# ProPrj_AmatronWithOpto_Flex_2026-01-19.net
KiCad netlist of a schematic drawn in EasyEDA Pro
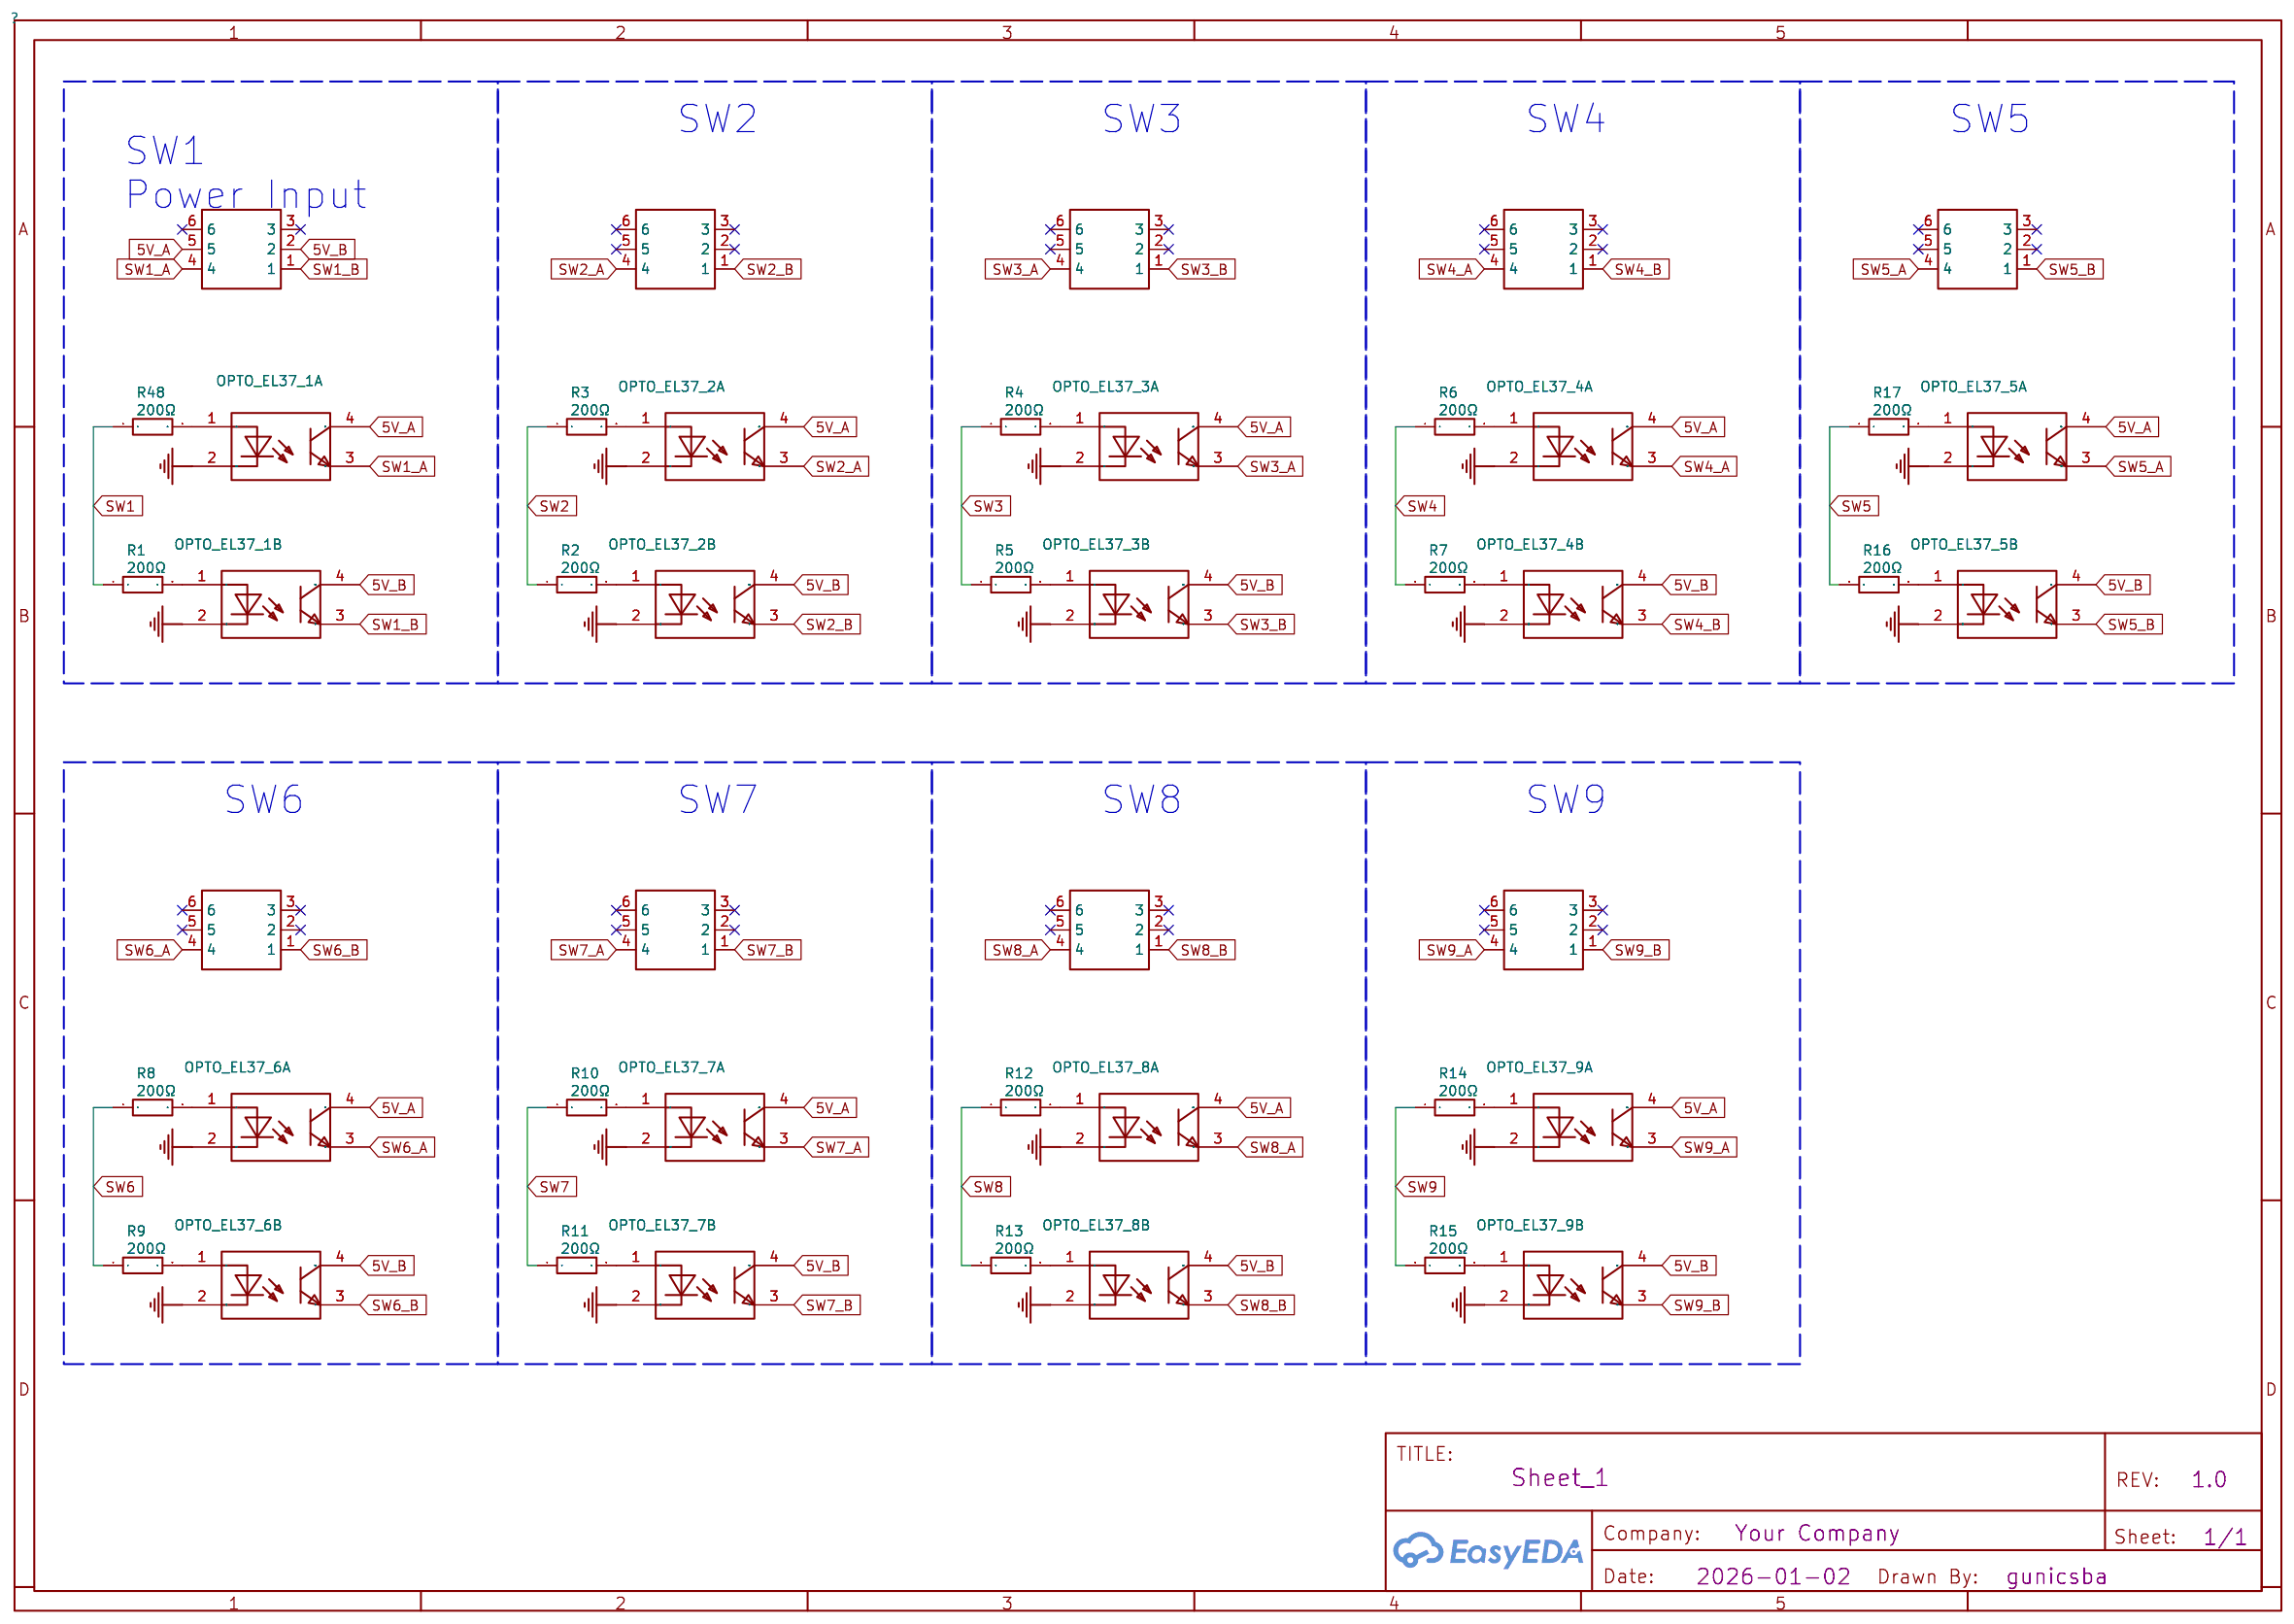
[diagram p0: SWITCH_OPTO]
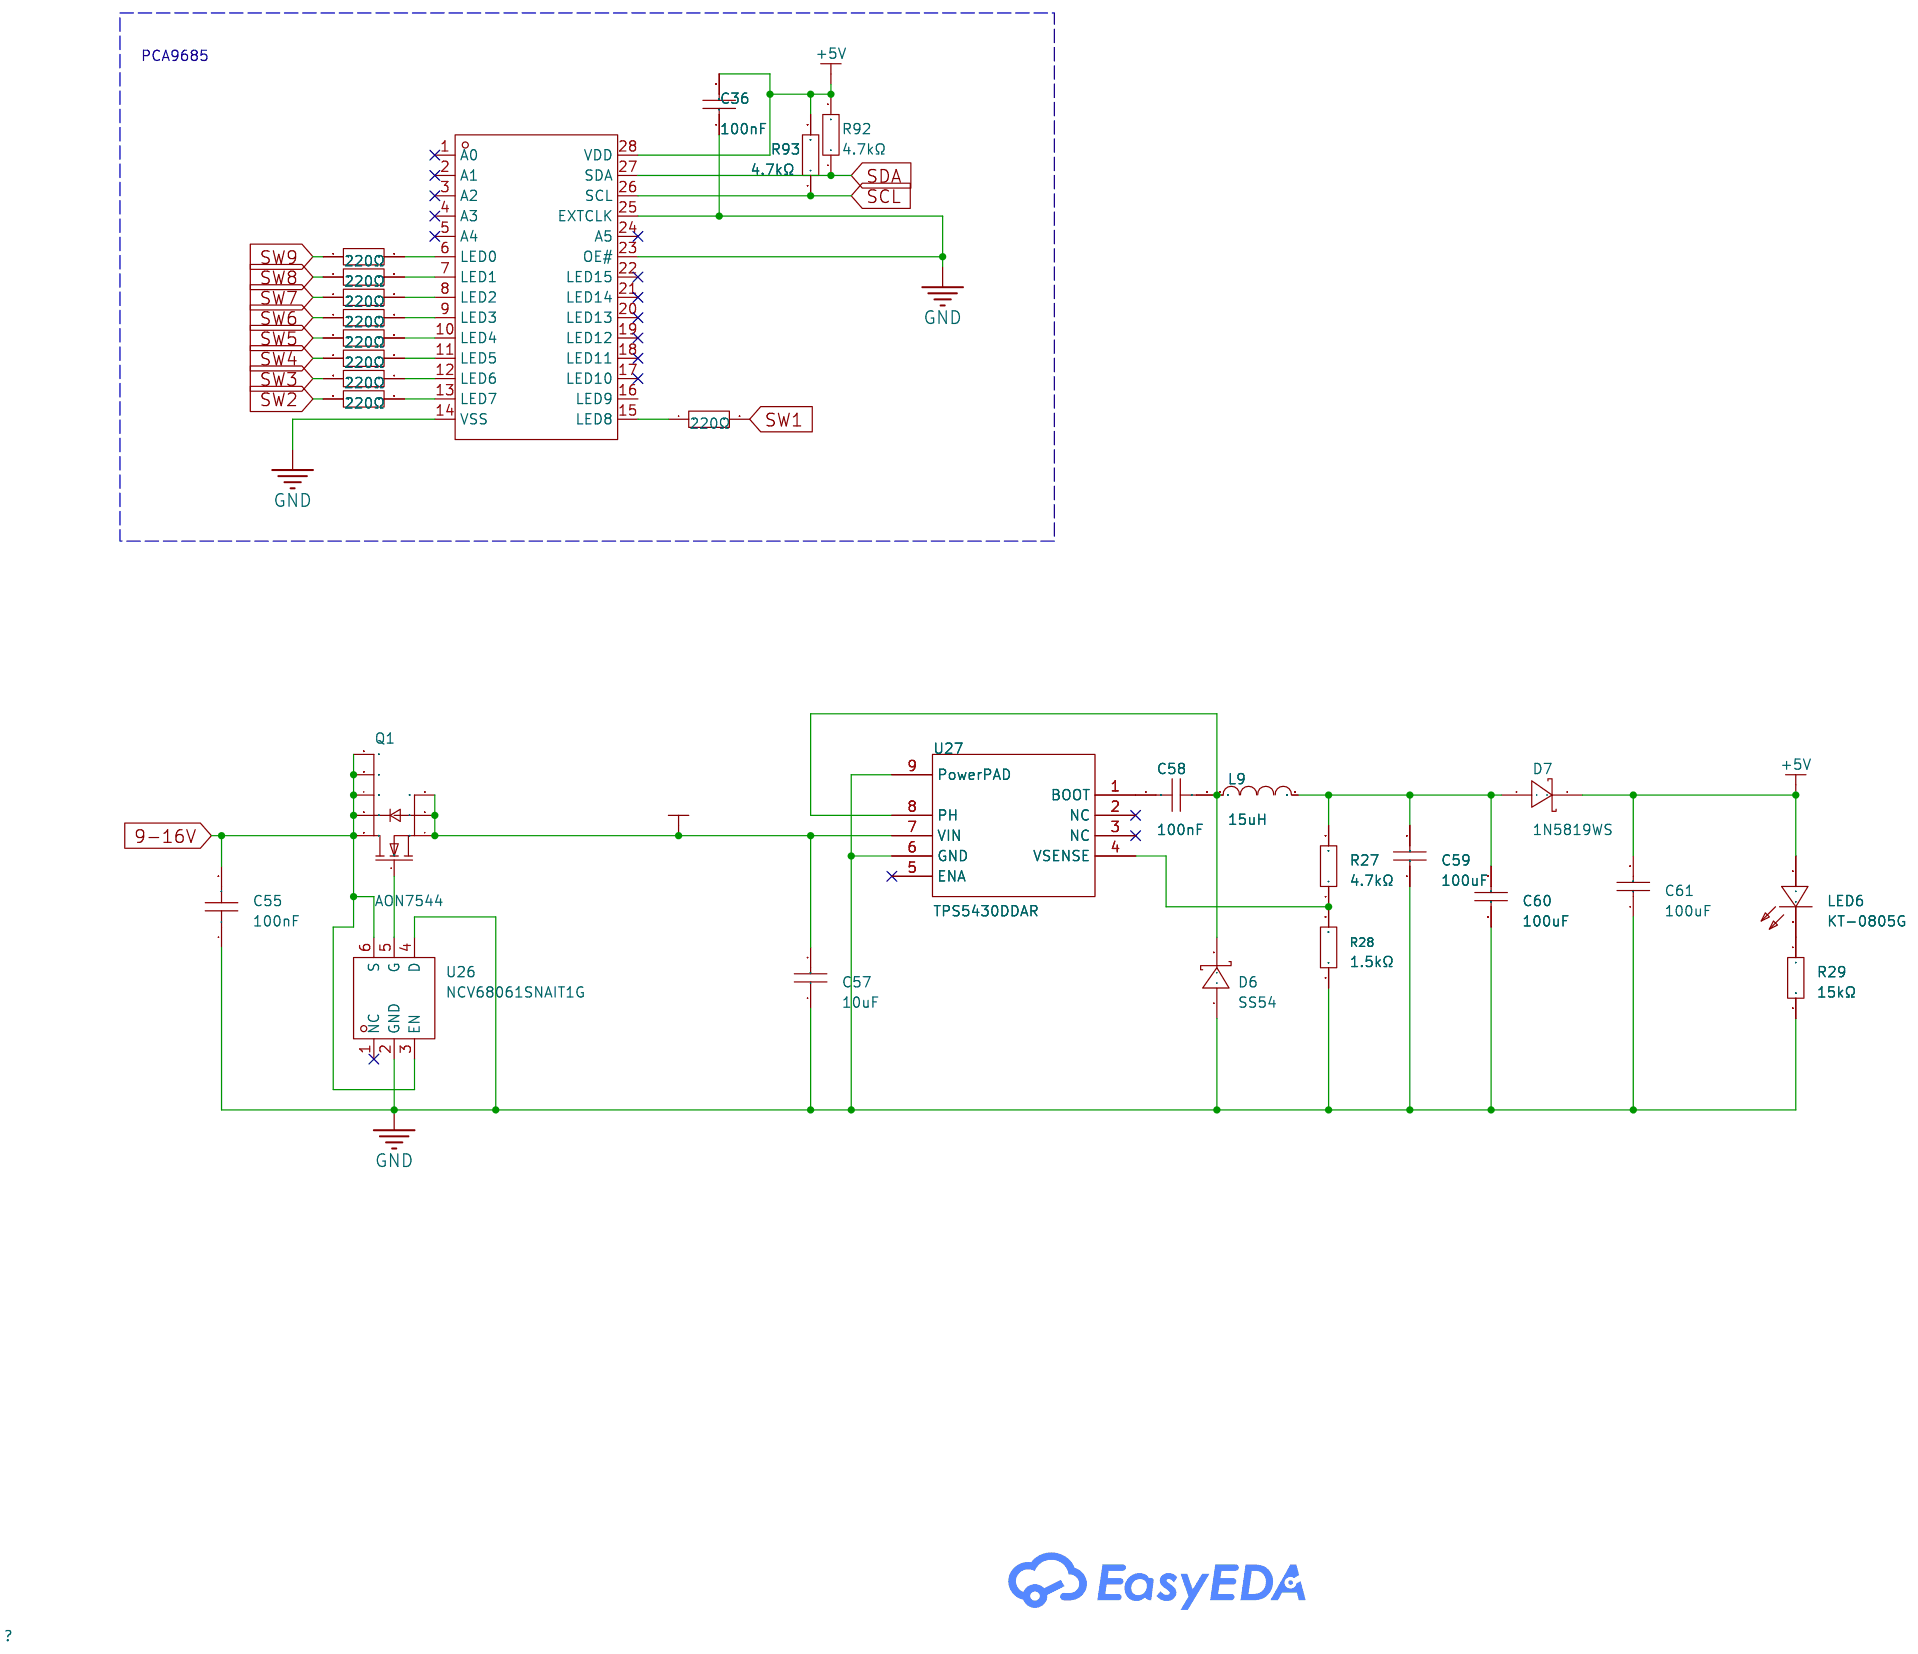
[diagram p1: DRIVER_POWER]

(export (version "E")
  (design (tool "Eeschema 10.0.6"))
  (components
    (comp (ref "OPTO_EL37_1A")
      (value "Speed Pulse")
      (footprint "easyedapro:SOP-4_L4.4-W2.8-P1.27-LS7.0-TL")
      (fields
        (field (name "Manufacturer Part") "EL3H7(B)(TA)-G")
        (field (name "Manufacturer") "EVERLIGHT(亿光)")
      )
      (libsource (lib "easyedapro") (part "Speed Pulse"))
    )
    (comp (ref "OPTO_EL37_1B")
      (value "Speed Pulse")
      (footprint "easyedapro:SOP-4_L4.4-W2.8-P1.27-LS7.0-TL")
      (fields
        (field (name "Manufacturer Part") "EL3H7(B)(TA)-G")
        (field (name "Manufacturer") "EVERLIGHT(亿光)")
      )
      (libsource (lib "easyedapro") (part "Speed Pulse"))
    )
    (comp (ref "OPTO_EL37_2A")
      (value "Speed Pulse")
      (footprint "easyedapro:SOP-4_L4.4-W2.8-P1.27-LS7.0-TL")
      (fields
        (field (name "Manufacturer Part") "EL3H7(B)(TA)-G")
        (field (name "Manufacturer") "EVERLIGHT(亿光)")
      )
      (libsource (lib "easyedapro") (part "Speed Pulse"))
    )
    (comp (ref "OPTO_EL37_2B")
      (value "Speed Pulse")
      (footprint "easyedapro:SOP-4_L4.4-W2.8-P1.27-LS7.0-TL")
      (fields
        (field (name "Manufacturer Part") "EL3H7(B)(TA)-G")
        (field (name "Manufacturer") "EVERLIGHT(亿光)")
      )
      (libsource (lib "easyedapro") (part "Speed Pulse"))
    )
    (comp (ref "OPTO_EL37_3A")
      (value "Speed Pulse")
      (footprint "easyedapro:SOP-4_L4.4-W2.8-P1.27-LS7.0-TL")
      (fields
        (field (name "Manufacturer Part") "EL3H7(B)(TA)-G")
        (field (name "Manufacturer") "EVERLIGHT(亿光)")
      )
      (libsource (lib "easyedapro") (part "Speed Pulse"))
    )
    (comp (ref "OPTO_EL37_3B")
      (value "Speed Pulse")
      (footprint "easyedapro:SOP-4_L4.4-W2.8-P1.27-LS7.0-TL")
      (fields
        (field (name "Manufacturer Part") "EL3H7(B)(TA)-G")
        (field (name "Manufacturer") "EVERLIGHT(亿光)")
      )
      (libsource (lib "easyedapro") (part "Speed Pulse"))
    )
    (comp (ref "OPTO_EL37_4A")
      (value "Speed Pulse")
      (footprint "easyedapro:SOP-4_L4.4-W2.8-P1.27-LS7.0-TL")
      (fields
        (field (name "Manufacturer Part") "EL3H7(B)(TA)-G")
        (field (name "Manufacturer") "EVERLIGHT(亿光)")
      )
      (libsource (lib "easyedapro") (part "Speed Pulse"))
    )
    (comp (ref "OPTO_EL37_4B")
      (value "Speed Pulse")
      (footprint "easyedapro:SOP-4_L4.4-W2.8-P1.27-LS7.0-TL")
      (fields
        (field (name "Manufacturer Part") "EL3H7(B)(TA)-G")
        (field (name "Manufacturer") "EVERLIGHT(亿光)")
      )
      (libsource (lib "easyedapro") (part "Speed Pulse"))
    )
    (comp (ref "OPTO_EL37_5A")
      (value "Speed Pulse")
      (footprint "easyedapro:SOP-4_L4.4-W2.8-P1.27-LS7.0-TL")
      (fields
        (field (name "Manufacturer Part") "EL3H7(B)(TA)-G")
        (field (name "Manufacturer") "EVERLIGHT(亿光)")
      )
      (libsource (lib "easyedapro") (part "Speed Pulse"))
    )
    (comp (ref "OPTO_EL37_5B")
      (value "Speed Pulse")
      (footprint "easyedapro:SOP-4_L4.4-W2.8-P1.27-LS7.0-TL")
      (fields
        (field (name "Manufacturer Part") "EL3H7(B)(TA)-G")
        (field (name "Manufacturer") "EVERLIGHT(亿光)")
      )
      (libsource (lib "easyedapro") (part "Speed Pulse"))
    )
    (comp (ref "OPTO_EL37_6A")
      (value "Speed Pulse")
      (footprint "easyedapro:SOP-4_L4.4-W2.8-P1.27-LS7.0-TL")
      (fields
        (field (name "Manufacturer Part") "EL3H7(B)(TA)-G")
        (field (name "Manufacturer") "EVERLIGHT(亿光)")
      )
      (libsource (lib "easyedapro") (part "Speed Pulse"))
    )
    (comp (ref "OPTO_EL37_6B")
      (value "Speed Pulse")
      (footprint "easyedapro:SOP-4_L4.4-W2.8-P1.27-LS7.0-TL")
      (fields
        (field (name "Manufacturer Part") "EL3H7(B)(TA)-G")
        (field (name "Manufacturer") "EVERLIGHT(亿光)")
      )
      (libsource (lib "easyedapro") (part "Speed Pulse"))
    )
    (comp (ref "OPTO_EL37_7A")
      (value "Speed Pulse")
      (footprint "easyedapro:SOP-4_L4.4-W2.8-P1.27-LS7.0-TL")
      (fields
        (field (name "Manufacturer Part") "EL3H7(B)(TA)-G")
        (field (name "Manufacturer") "EVERLIGHT(亿光)")
      )
      (libsource (lib "easyedapro") (part "Speed Pulse"))
    )
    (comp (ref "OPTO_EL37_7B")
      (value "Speed Pulse")
      (footprint "easyedapro:SOP-4_L4.4-W2.8-P1.27-LS7.0-TL")
      (fields
        (field (name "Manufacturer Part") "EL3H7(B)(TA)-G")
        (field (name "Manufacturer") "EVERLIGHT(亿光)")
      )
      (libsource (lib "easyedapro") (part "Speed Pulse"))
    )
    (comp (ref "OPTO_EL37_8A")
      (value "Speed Pulse")
      (footprint "easyedapro:SOP-4_L4.4-W2.8-P1.27-LS7.0-TL")
      (fields
        (field (name "Manufacturer Part") "EL3H7(B)(TA)-G")
        (field (name "Manufacturer") "EVERLIGHT(亿光)")
      )
      (libsource (lib "easyedapro") (part "Speed Pulse"))
    )
    (comp (ref "OPTO_EL37_8B")
      (value "Speed Pulse")
      (footprint "easyedapro:SOP-4_L4.4-W2.8-P1.27-LS7.0-TL")
      (fields
        (field (name "Manufacturer Part") "EL3H7(B)(TA)-G")
        (field (name "Manufacturer") "EVERLIGHT(亿光)")
      )
      (libsource (lib "easyedapro") (part "Speed Pulse"))
    )
    (comp (ref "OPTO_EL37_9A")
      (value "Speed Pulse")
      (footprint "easyedapro:SOP-4_L4.4-W2.8-P1.27-LS7.0-TL")
      (fields
        (field (name "Manufacturer Part") "EL3H7(B)(TA)-G")
        (field (name "Manufacturer") "EVERLIGHT(亿光)")
      )
      (libsource (lib "easyedapro") (part "Speed Pulse"))
    )
    (comp (ref "OPTO_EL37_9B")
      (value "Speed Pulse")
      (footprint "easyedapro:SOP-4_L4.4-W2.8-P1.27-LS7.0-TL")
      (fields
        (field (name "Manufacturer Part") "EL3H7(B)(TA)-G")
        (field (name "Manufacturer") "EVERLIGHT(亿光)")
      )
      (libsource (lib "easyedapro") (part "Speed Pulse"))
    )
    (comp (ref "R1")
      (value "200Ω")
      (footprint "easyedapro:R0805")
      (fields
        (field (name "Manufacturer Part") "0805W8F2000T5E")
        (field (name "Manufacturer") "UNI-ROYAL(厚声)")
      )
      (libsource (lib "easyedapro") (part "200Ω"))
    )
    (comp (ref "R2")
      (value "200Ω")
      (footprint "easyedapro:R0805")
      (fields
        (field (name "Manufacturer Part") "0805W8F2000T5E")
        (field (name "Manufacturer") "UNI-ROYAL(厚声)")
      )
      (libsource (lib "easyedapro") (part "200Ω"))
    )
    (comp (ref "R3")
      (value "200Ω")
      (footprint "easyedapro:R0805")
      (fields
        (field (name "Manufacturer Part") "0805W8F2000T5E")
        (field (name "Manufacturer") "UNI-ROYAL(厚声)")
      )
      (libsource (lib "easyedapro") (part "200Ω"))
    )
    (comp (ref "R4")
      (value "200Ω")
      (footprint "easyedapro:R0805")
      (fields
        (field (name "Manufacturer Part") "0805W8F2000T5E")
        (field (name "Manufacturer") "UNI-ROYAL(厚声)")
      )
      (libsource (lib "easyedapro") (part "200Ω"))
    )
    (comp (ref "R5")
      (value "200Ω")
      (footprint "easyedapro:R0805")
      (fields
        (field (name "Manufacturer Part") "0805W8F2000T5E")
        (field (name "Manufacturer") "UNI-ROYAL(厚声)")
      )
      (libsource (lib "easyedapro") (part "200Ω"))
    )
    (comp (ref "R6")
      (value "200Ω")
      (footprint "easyedapro:R0805")
      (fields
        (field (name "Manufacturer Part") "0805W8F2000T5E")
        (field (name "Manufacturer") "UNI-ROYAL(厚声)")
      )
      (libsource (lib "easyedapro") (part "200Ω"))
    )
    (comp (ref "R7")
      (value "200Ω")
      (footprint "easyedapro:R0805")
      (fields
        (field (name "Manufacturer Part") "0805W8F2000T5E")
        (field (name "Manufacturer") "UNI-ROYAL(厚声)")
      )
      (libsource (lib "easyedapro") (part "200Ω"))
    )
    (comp (ref "R8")
      (value "200Ω")
      (footprint "easyedapro:R0805")
      (fields
        (field (name "Manufacturer Part") "0805W8F2000T5E")
        (field (name "Manufacturer") "UNI-ROYAL(厚声)")
      )
      (libsource (lib "easyedapro") (part "200Ω"))
    )
    (comp (ref "R9")
      (value "200Ω")
      (footprint "easyedapro:R0805")
      (fields
        (field (name "Manufacturer Part") "0805W8F2000T5E")
        (field (name "Manufacturer") "UNI-ROYAL(厚声)")
      )
      (libsource (lib "easyedapro") (part "200Ω"))
    )
    (comp (ref "R10")
      (value "200Ω")
      (footprint "easyedapro:R0805")
      (fields
        (field (name "Manufacturer Part") "0805W8F2000T5E")
        (field (name "Manufacturer") "UNI-ROYAL(厚声)")
      )
      (libsource (lib "easyedapro") (part "200Ω"))
    )
    (comp (ref "R11")
      (value "200Ω")
      (footprint "easyedapro:R0805")
      (fields
        (field (name "Manufacturer Part") "0805W8F2000T5E")
        (field (name "Manufacturer") "UNI-ROYAL(厚声)")
      )
      (libsource (lib "easyedapro") (part "200Ω"))
    )
    (comp (ref "R12")
      (value "200Ω")
      (footprint "easyedapro:R0805")
      (fields
        (field (name "Manufacturer Part") "0805W8F2000T5E")
        (field (name "Manufacturer") "UNI-ROYAL(厚声)")
      )
      (libsource (lib "easyedapro") (part "200Ω"))
    )
    (comp (ref "R13")
      (value "200Ω")
      (footprint "easyedapro:R0805")
      (fields
        (field (name "Manufacturer Part") "0805W8F2000T5E")
        (field (name "Manufacturer") "UNI-ROYAL(厚声)")
      )
      (libsource (lib "easyedapro") (part "200Ω"))
    )
    (comp (ref "R14")
      (value "200Ω")
      (footprint "easyedapro:R0805")
      (fields
        (field (name "Manufacturer Part") "0805W8F2000T5E")
        (field (name "Manufacturer") "UNI-ROYAL(厚声)")
      )
      (libsource (lib "easyedapro") (part "200Ω"))
    )
    (comp (ref "R15")
      (value "200Ω")
      (footprint "easyedapro:R0805")
      (fields
        (field (name "Manufacturer Part") "0805W8F2000T5E")
        (field (name "Manufacturer") "UNI-ROYAL(厚声)")
      )
      (libsource (lib "easyedapro") (part "200Ω"))
    )
    (comp (ref "R16")
      (value "200Ω")
      (footprint "easyedapro:R0805")
      (fields
        (field (name "Manufacturer Part") "0805W8F2000T5E")
        (field (name "Manufacturer") "UNI-ROYAL(厚声)")
      )
      (libsource (lib "easyedapro") (part "200Ω"))
    )
    (comp (ref "R17")
      (value "200Ω")
      (footprint "easyedapro:R0805")
      (fields
        (field (name "Manufacturer Part") "0805W8F2000T5E")
        (field (name "Manufacturer") "UNI-ROYAL(厚声)")
      )
      (libsource (lib "easyedapro") (part "200Ω"))
    )
    (comp (ref "R48")
      (value "200Ω")
      (footprint "easyedapro:R0805")
      (fields
        (field (name "Manufacturer Part") "0805W8F2000T5E")
        (field (name "Manufacturer") "UNI-ROYAL(厚声)")
      )
      (libsource (lib "easyedapro") (part "200Ω"))
    )
    (comp (ref "U1")
      (value "1MD1T1B1M1QES-5")
      (footprint "easyedapro:SW-TH_6P-L12.7-W11.4-P4.7-LS4.8_1MD1T1B1M1QES-5")
      (fields (field (name "Manufacturer") "Dailywell(德利威)") (field (name "Contributor") "lcsc"))
      (libsource (lib "easyedapro") (part "1MD1T1B1M1QES-5"))
    )
    (comp (ref "U2")
      (value "1MD1T1B1M1QES-5")
      (footprint "easyedapro:SW-TH_6P-L12.7-W11.4-P4.7-LS4.8_1MD1T1B1M1QES-5")
      (fields (field (name "Manufacturer") "Dailywell(德利威)") (field (name "Contributor") "lcsc"))
      (libsource (lib "easyedapro") (part "1MD1T1B1M1QES-5"))
    )
    (comp (ref "U3")
      (value "1MD1T1B1M1QES-5")
      (footprint "easyedapro:SW-TH_6P-L12.7-W11.4-P4.7-LS4.8_1MD1T1B1M1QES-5")
      (fields (field (name "Manufacturer") "Dailywell(德利威)") (field (name "Contributor") "lcsc"))
      (libsource (lib "easyedapro") (part "1MD1T1B1M1QES-5"))
    )
    (comp (ref "U4")
      (value "1MD1T1B1M1QES-5")
      (footprint "easyedapro:SW-TH_6P-L12.7-W11.4-P4.7-LS4.8_1MD1T1B1M1QES-5")
      (fields (field (name "Manufacturer") "Dailywell(德利威)") (field (name "Contributor") "lcsc"))
      (libsource (lib "easyedapro") (part "1MD1T1B1M1QES-5"))
    )
    (comp (ref "U5")
      (value "1MD1T1B1M1QES-5")
      (footprint "easyedapro:SW-TH_6P-L12.7-W11.4-P4.7-LS4.8_1MD1T1B1M1QES-5")
      (fields (field (name "Manufacturer") "Dailywell(德利威)") (field (name "Contributor") "lcsc"))
      (libsource (lib "easyedapro") (part "1MD1T1B1M1QES-5"))
    )
    (comp (ref "U6")
      (value "1MD1T1B1M1QES-5")
      (footprint "easyedapro:SW-TH_6P-L12.7-W11.4-P4.7-LS4.8_1MD1T1B1M1QES-5")
      (fields (field (name "Manufacturer") "Dailywell(德利威)") (field (name "Contributor") "lcsc"))
      (libsource (lib "easyedapro") (part "1MD1T1B1M1QES-5"))
    )
    (comp (ref "U7")
      (value "1MD1T1B1M1QES-5")
      (footprint "easyedapro:SW-TH_6P-L12.7-W11.4-P4.7-LS4.8_1MD1T1B1M1QES-5")
      (fields (field (name "Manufacturer") "Dailywell(德利威)") (field (name "Contributor") "lcsc"))
      (libsource (lib "easyedapro") (part "1MD1T1B1M1QES-5"))
    )
    (comp (ref "U8")
      (value "1MD1T1B1M1QES-5")
      (footprint "easyedapro:SW-TH_6P-L12.7-W11.4-P4.7-LS4.8_1MD1T1B1M1QES-5")
      (fields (field (name "Manufacturer") "Dailywell(德利威)") (field (name "Contributor") "lcsc"))
      (libsource (lib "easyedapro") (part "1MD1T1B1M1QES-5"))
    )
    (comp (ref "U9")
      (value "1MD1T1B1M1QES-5")
      (footprint "easyedapro:SW-TH_6P-L12.7-W11.4-P4.7-LS4.8_1MD1T1B1M1QES-5")
      (fields (field (name "Manufacturer") "Dailywell(德利威)") (field (name "Contributor") "lcsc"))
      (libsource (lib "easyedapro") (part "1MD1T1B1M1QES-5"))
    )
    (comp (ref "C36")
      (value "100nF")
      (footprint "easyedapro:C0402")
      (fields
        (field (name "Manufacturer Part") "CL05B104KO5NNNC")
        (field (name "Manufacturer") "SAMSUNG(三星)")
      )
      (libsource (lib "easyedapro") (part "CL05B104KO5NNNC"))
    )
    (comp (ref "C55")
      (value "100nF")
      (footprint "easyedapro:C0603")
      (description "Capacitance:100nF Tolerance:±10% Tolerance:±10% Voltage Rating:50V Temperature Coefficient:X7R")
      (fields
        (field (name "Manufacturer Part") "CC0603KRX7R9BB104")
        (field (name "Manufacturer") "YAGEO(国巨)")
      )
      (libsource (lib "easyedapro") (part "CC0603KRX7R9BB104"))
    )
    (comp (ref "C57")
      (value "10uF")
      (footprint "easyedapro:C1206")
      (description "Capacitance:10uF Tolerance:±10% Tolerance:±10% Voltage Rating:50V Temperature Coefficient:X5R")
      (fields
        (field (name "Manufacturer Part") "CL31A106KBHNNNE")
        (field (name "Manufacturer") "SAMSUNG(三星)")
      )
      (libsource (lib "easyedapro") (part "CL31A106KBHNNNE"))
    )
    (comp (ref "C58")
      (value "100nF")
      (footprint "easyedapro:C0603")
      (description "Capacitance:100nF Tolerance:±10% Tolerance:±10% Voltage Rating:50V Temperature Coefficient:X7R")
      (fields
        (field (name "Manufacturer Part") "CC0603KRX7R9BB104")
        (field (name "Manufacturer") "YAGEO(国巨)")
      )
      (libsource (lib "easyedapro") (part "CC0603KRX7R9BB104"))
    )
    (comp (ref "C59")
      (value "100uF")
      (footprint "easyedapro:C1206")
      (description "Capacitance:100uF Tolerance:±20% Tolerance:±20% Voltage Rating:6.3V Temperature Coefficient:X5R")
      (fields
        (field (name "Manufacturer Part") "CL31A107MQHNNNE")
        (field (name "Manufacturer") "SAMSUNG(三星)")
      )
      (libsource (lib "easyedapro") (part "CL31A107MQHNNNE"))
    )
    (comp (ref "C60")
      (value "100uF")
      (footprint "easyedapro:C1206")
      (description "Capacitance:100uF Tolerance:±20% Tolerance:±20% Voltage Rating:6.3V Temperature Coefficient:X5R")
      (fields
        (field (name "Manufacturer Part") "CL31A107MQHNNNE")
        (field (name "Manufacturer") "SAMSUNG(三星)")
      )
      (libsource (lib "easyedapro") (part "CL31A107MQHNNNE"))
    )
    (comp (ref "C61")
      (value "100uF")
      (footprint "easyedapro:C1206")
      (description "Capacitance:100uF Tolerance:±20% Tolerance:±20% Voltage Rating:6.3V Temperature Coefficient:X5R")
      (fields
        (field (name "Manufacturer Part") "CL31A107MQHNNNE")
        (field (name "Manufacturer") "SAMSUNG(三星)")
      )
      (libsource (lib "easyedapro") (part "CL31A107MQHNNNE"))
    )
    (comp (ref "D6")
      (value "SS54")
      (footprint "easyedapro:SMA_L4.4-W2.8-LS5.4-R-RD")
      (fields (field (name "Manufacturer") "MDD(辰达半导体)"))
      (libsource (lib "easyedapro") (part "SS54_C22452"))
    )
    (comp (ref "D7")
      (value "1N5819WS")
      (footprint "easyedapro:SOD-323_L1.8-W1.3-LS2.5-RD")
      (fields (field (name "Manufacturer") "Hottech(合科泰)"))
      (libsource (lib "easyedapro") (part "1N5819WS"))
    )
    (comp (ref "L9")
      (value "15uH")
      (footprint "easyedapro:IND-SMD_L7.0-W6.6_FXL0630")
      (fields (field (name "Manufacturer Part") "FXL0630-150-M") (field (name "Manufacturer") "cjiang(长江微电)"))
      (libsource (lib "easyedapro") (part "FXL0630-150-M"))
    )
    (comp (ref "LED6")
      (value "KT-0805G")
      (footprint "easyedapro:LED0805-R-RD")
      (fields (field (name "Manufacturer") "KENTO"))
      (libsource (lib "easyedapro") (part "0805G (Green)"))
    )
    (comp (ref "Q1")
      (value "AON7544")
      (footprint "easyedapro:DFN-8_L3.2-W3.1-P0.65-LS3.4-BL")
      (fields (field (name "Manufacturer") "HXY MOSFET(华轩阳电子)"))
      (libsource (lib "easyedapro") (part "AON7544_C5261066"))
    )
    (comp (ref "R27")
      (value "4.7kΩ")
      (fields
        (field (name "Manufacturer Part") "0402WGF4701TCE")
        (field (name "Manufacturer") "UNI-ROYAL(厚声)")
      )
      (libsource (lib "easyedapro") (part "0402WGJ0472TCE"))
    )
    (comp (ref "R28")
      (value "1.5kΩ")
      (footprint "easyedapro:R0402")
      (fields
        (field (name "Manufacturer Part") "0402WGF1501TCE")
        (field (name "Manufacturer") "UNI-ROYAL(厚声)")
      )
      (libsource (lib "easyedapro") (part "0402WGF1501TCE"))
    )
    (comp (ref "R29")
      (value "15kΩ")
      (footprint "easyedapro:R0402")
      (description "电阻类型:厚膜电阻;阻值:15kΩ;精度:±1%;功率:62.5mW;")
      (fields
        (field (name "Manufacturer Part") "0402WGF1502TCE")
        (field (name "Manufacturer") "UNI-ROYAL(厚声)")
      )
      (libsource (lib "easyedapro") (part "0402WGF1502TCE"))
    )
    (comp (ref "R50") (value "220Ω") (libsource (lib "easyedapro") (part "Res")))
    (comp (ref "R51") (value "220Ω") (libsource (lib "easyedapro") (part "Res")))
    (comp (ref "R52") (value "220Ω") (libsource (lib "easyedapro") (part "Res")))
    (comp (ref "R53") (value "220Ω") (libsource (lib "easyedapro") (part "Res")))
    (comp (ref "R54") (value "220Ω") (libsource (lib "easyedapro") (part "Res")))
    (comp (ref "R55") (value "220Ω") (libsource (lib "easyedapro") (part "Res")))
    (comp (ref "R63") (value "220Ω") (libsource (lib "easyedapro") (part "Res")))
    (comp (ref "R64") (value "220Ω") (libsource (lib "easyedapro") (part "Res")))
    (comp (ref "R65") (value "220Ω") (libsource (lib "easyedapro") (part "Res")))
    (comp (ref "R92")
      (value "4.7kΩ")
      (fields
        (field (name "Manufacturer Part") "0805W8F4701T5E")
        (field (name "Manufacturer") "UNI-ROYAL(厚声)")
      )
      (libsource (lib "easyedapro") (part "MR04X4701FTL"))
    )
    (comp (ref "R93")
      (value "4.7kΩ")
      (fields
        (field (name "Manufacturer Part") "0805W8F4701T5E")
        (field (name "Manufacturer") "UNI-ROYAL(厚声)")
      )
      (libsource (lib "easyedapro") (part "MR04X4701FTL"))
    )
    (comp (ref "U19")
      (value "~")
      (footprint "easyedapro:TSSOP-28_L9.7-W4.4-P0.65-LS6.4-TL")
      (fields (field (name "Manufacturer Part") "PCA9685PW,118") (field (name "Manufacturer") "NXP(恩智浦)"))
      (libsource (lib "easyedapro") (part "PCA9685PW,118"))
    )
    (comp (ref "U26")
      (value "NCV68061SNAIT1G")
      (footprint "easyedapro:TSOP-6_L3.0-W1.5-P0.95-BL")
      (fields (field (name "Manufacturer") "onsemi(安森美)"))
      (libsource (lib "easyedapro") (part "NCV68061SNAIT1G"))
    )
    (comp (ref "U27")
      (value "TPS5430DDAR")
      (footprint "easyedapro:ESOP-8_L4.9-W3.9-P1.27-LS6.0-TL-EP")
      (fields (field (name "Manufacturer") "TI(德州仪器)"))
      (libsource (lib "easyedapro") (part "TPS5430DDAR"))
    )
  )
  (nets
    (net (code "1") (name "+5V") (class "Default")
      (node (ref "C36") (pin "2") (pinfunction "2_2") (pintype "input"))
      (node (ref "C61") (pin "2") (pinfunction "2_2") (pintype "input"))
      (node (ref "D7") (pin "1") (pinfunction "K_1") (pintype "unspecified"))
      (node (ref "LED6") (pin "1") (pinfunction "A_1") (pintype "unspecified"))
      (node (ref "R92") (pin "2") (pinfunction "2_2") (pintype "input"))
      (node (ref "R93") (pin "2") (pinfunction "2_2") (pintype "input"))
      (node (ref "U19") (pin "28") (pinfunction "VDD_28") (pintype "input"))
    )
    (net (code "2") (name "+12V") (class "Default")
      (node (ref "C57") (pin "2") (pinfunction "2_2") (pintype "input"))
      (node (ref "Q1") (pin "1") (pinfunction "S_1") (pintype "unspecified"))
      (node (ref "Q1") (pin "2") (pinfunction "S_2") (pintype "unspecified"))
      (node (ref "Q1") (pin "3") (pinfunction "S_3") (pintype "unspecified"))
      (node (ref "U27") (pin "7") (pinfunction "VIN_7") (pintype "unspecified"))
    )
    (net (code "3") (name "5V_A") (class "Default")
      (node (ref "OPTO_EL37_1A") (pin "4") (pinfunction "COL_4") (pintype "unspecified"))
      (node (ref "OPTO_EL37_2A") (pin "4") (pinfunction "COL_4") (pintype "unspecified"))
      (node (ref "OPTO_EL37_3A") (pin "4") (pinfunction "COL_4") (pintype "unspecified"))
      (node (ref "OPTO_EL37_4A") (pin "4") (pinfunction "COL_4") (pintype "unspecified"))
      (node (ref "OPTO_EL37_5A") (pin "4") (pinfunction "COL_4") (pintype "unspecified"))
      (node (ref "OPTO_EL37_6A") (pin "4") (pinfunction "COL_4") (pintype "unspecified"))
      (node (ref "OPTO_EL37_7A") (pin "4") (pinfunction "COL_4") (pintype "unspecified"))
      (node (ref "OPTO_EL37_8A") (pin "4") (pinfunction "COL_4") (pintype "unspecified"))
      (node (ref "OPTO_EL37_9A") (pin "4") (pinfunction "COL_4") (pintype "unspecified"))
      (node (ref "U1") (pin "5") (pinfunction "5_5") (pintype "unspecified"))
    )
    (net (code "4") (name "5V_B") (class "Default")
      (node (ref "OPTO_EL37_1B") (pin "4") (pinfunction "COL_4") (pintype "unspecified"))
      (node (ref "OPTO_EL37_2B") (pin "4") (pinfunction "COL_4") (pintype "unspecified"))
      (node (ref "OPTO_EL37_3B") (pin "4") (pinfunction "COL_4") (pintype "unspecified"))
      (node (ref "OPTO_EL37_4B") (pin "4") (pinfunction "COL_4") (pintype "unspecified"))
      (node (ref "OPTO_EL37_5B") (pin "4") (pinfunction "COL_4") (pintype "unspecified"))
      (node (ref "OPTO_EL37_6B") (pin "4") (pinfunction "COL_4") (pintype "unspecified"))
      (node (ref "OPTO_EL37_7B") (pin "4") (pinfunction "COL_4") (pintype "unspecified"))
      (node (ref "OPTO_EL37_8B") (pin "4") (pinfunction "COL_4") (pintype "unspecified"))
      (node (ref "OPTO_EL37_9B") (pin "4") (pinfunction "COL_4") (pintype "unspecified"))
      (node (ref "U1") (pin "2") (pinfunction "2_2") (pintype "unspecified"))
    )
    (net (code "5") (name "9-16V") (class "Default")
      (node (ref "C55") (pin "2") (pinfunction "2_2") (pintype "unspecified"))
      (node (ref "Q1") (pin "5") (pinfunction "D_5") (pintype "unspecified"))
      (node (ref "Q1") (pin "6") (pinfunction "D_6") (pintype "unspecified"))
      (node (ref "Q1") (pin "7") (pinfunction "D_7") (pintype "unspecified"))
      (node (ref "Q1") (pin "8") (pinfunction "D_8") (pintype "unspecified"))
      (node (ref "Q1") (pin "9") (pinfunction "D_9") (pintype "unspecified"))
      (node (ref "U26") (pin "3") (pinfunction "EN_3") (pintype "unspecified"))
      (node (ref "U26") (pin "6") (pinfunction "S_6") (pintype "unspecified"))
    )
    (net (code "6") (name "GND") (class "Default")
      (node (ref "C36") (pin "1") (pinfunction "1_1") (pintype "input"))
      (node (ref "C55") (pin "1") (pinfunction "1_1") (pintype "unspecified"))
      (node (ref "C57") (pin "1") (pinfunction "1_1") (pintype "input"))
      (node (ref "C59") (pin "1") (pinfunction "1_1") (pintype "input"))
      (node (ref "C60") (pin "1") (pinfunction "1_1") (pintype "input"))
      (node (ref "C61") (pin "1") (pinfunction "1_1") (pintype "input"))
      (node (ref "D6") (pin "1") (pinfunction "A_1") (pintype "unspecified"))
      (node (ref "OPTO_EL37_1A") (pin "2") (pinfunction "CAT_2") (pintype "unspecified"))
      (node (ref "OPTO_EL37_1B") (pin "2") (pinfunction "CAT_2") (pintype "unspecified"))
      (node (ref "OPTO_EL37_2A") (pin "2") (pinfunction "CAT_2") (pintype "unspecified"))
      (node (ref "OPTO_EL37_2B") (pin "2") (pinfunction "CAT_2") (pintype "unspecified"))
      (node (ref "OPTO_EL37_3A") (pin "2") (pinfunction "CAT_2") (pintype "unspecified"))
      (node (ref "OPTO_EL37_3B") (pin "2") (pinfunction "CAT_2") (pintype "unspecified"))
      (node (ref "OPTO_EL37_4A") (pin "2") (pinfunction "CAT_2") (pintype "unspecified"))
      (node (ref "OPTO_EL37_4B") (pin "2") (pinfunction "CAT_2") (pintype "unspecified"))
      (node (ref "OPTO_EL37_5A") (pin "2") (pinfunction "CAT_2") (pintype "unspecified"))
      (node (ref "OPTO_EL37_5B") (pin "2") (pinfunction "CAT_2") (pintype "unspecified"))
      (node (ref "OPTO_EL37_6A") (pin "2") (pinfunction "CAT_2") (pintype "unspecified"))
      (node (ref "OPTO_EL37_6B") (pin "2") (pinfunction "CAT_2") (pintype "unspecified"))
      (node (ref "OPTO_EL37_7A") (pin "2") (pinfunction "CAT_2") (pintype "unspecified"))
      (node (ref "OPTO_EL37_7B") (pin "2") (pinfunction "CAT_2") (pintype "unspecified"))
      (node (ref "OPTO_EL37_8A") (pin "2") (pinfunction "CAT_2") (pintype "unspecified"))
      (node (ref "OPTO_EL37_8B") (pin "2") (pinfunction "CAT_2") (pintype "unspecified"))
      (node (ref "OPTO_EL37_9A") (pin "2") (pinfunction "CAT_2") (pintype "unspecified"))
      (node (ref "OPTO_EL37_9B") (pin "2") (pinfunction "CAT_2") (pintype "unspecified"))
      (node (ref "R28") (pin "1") (pinfunction "1_1") (pintype "input"))
      (node (ref "R29") (pin "2") (pinfunction "2_2") (pintype "input"))
      (node (ref "U19") (pin "14") (pinfunction "VSS_14") (pintype "input"))
      (node (ref "U19") (pin "23") (pinfunction "OE#_23") (pintype "input"))
      (node (ref "U19") (pin "25") (pinfunction "EXTCLK_25") (pintype "input"))
      (node (ref "U26") (pin "2") (pinfunction "GND_2") (pintype "unspecified"))
      (node (ref "U26") (pin "4") (pinfunction "D_4") (pintype "unspecified"))
      (node (ref "U27") (pin "6") (pinfunction "GND_6") (pintype "unspecified"))
      (node (ref "U27") (pin "9") (pinfunction "PowerPAD_9") (pintype "unspecified"))
    )
    (net (code "7") (name "Net-(D6-K)") (class "Default")
      (node (ref "C58") (pin "2") (pinfunction "2_2") (pintype "unspecified"))
      (node (ref "D6") (pin "2") (pinfunction "K_2") (pintype "unspecified"))
      (node (ref "L9") (pin "1") (pinfunction "1_1") (pintype "unspecified"))
      (node (ref "U27") (pin "8") (pinfunction "PH_8") (pintype "unspecified"))
    )
    (net (code "8") (name "Net-(D7-A)") (class "Default")
      (node (ref "C59") (pin "2") (pinfunction "2_2") (pintype "input"))
      (node (ref "C60") (pin "2") (pinfunction "2_2") (pintype "input"))
      (node (ref "D7") (pin "2") (pinfunction "A_2") (pintype "unspecified"))
      (node (ref "L9") (pin "2") (pinfunction "2_2") (pintype "unspecified"))
      (node (ref "R27") (pin "2") (pinfunction "2_2") (pintype "input"))
    )
    (net (code "9") (name "Net-(LED6-K)") (class "Default")
      (node (ref "LED6") (pin "2") (pinfunction "K_2") (pintype "unspecified"))
      (node (ref "R29") (pin "1") (pinfunction "1_1") (pintype "input"))
    )
    (net (code "10") (name "Net-(OPTO_EL37_1A-AN)") (class "Default")
      (node (ref "OPTO_EL37_1A") (pin "1") (pinfunction "AN_1") (pintype "unspecified"))
      (node (ref "R48") (pin "2") (pinfunction "2_2") (pintype "input"))
    )
    (net (code "11") (name "Net-(OPTO_EL37_1B-AN)") (class "Default")
      (node (ref "OPTO_EL37_1B") (pin "1") (pinfunction "AN_1") (pintype "unspecified"))
      (node (ref "R1") (pin "2") (pinfunction "2_2") (pintype "input"))
    )
    (net (code "12") (name "Net-(OPTO_EL37_2A-AN)") (class "Default")
      (node (ref "OPTO_EL37_2A") (pin "1") (pinfunction "AN_1") (pintype "unspecified"))
      (node (ref "R3") (pin "2") (pinfunction "2_2") (pintype "input"))
    )
    (net (code "13") (name "Net-(OPTO_EL37_2B-AN)") (class "Default")
      (node (ref "OPTO_EL37_2B") (pin "1") (pinfunction "AN_1") (pintype "unspecified"))
      (node (ref "R2") (pin "2") (pinfunction "2_2") (pintype "input"))
    )
    (net (code "14") (name "Net-(OPTO_EL37_3A-AN)") (class "Default")
      (node (ref "OPTO_EL37_3A") (pin "1") (pinfunction "AN_1") (pintype "unspecified"))
      (node (ref "R4") (pin "2") (pinfunction "2_2") (pintype "input"))
    )
    (net (code "15") (name "Net-(OPTO_EL37_3B-AN)") (class "Default")
      (node (ref "OPTO_EL37_3B") (pin "1") (pinfunction "AN_1") (pintype "unspecified"))
      (node (ref "R5") (pin "2") (pinfunction "2_2") (pintype "input"))
    )
    (net (code "16") (name "Net-(OPTO_EL37_4A-AN)") (class "Default")
      (node (ref "OPTO_EL37_4A") (pin "1") (pinfunction "AN_1") (pintype "unspecified"))
      (node (ref "R6") (pin "2") (pinfunction "2_2") (pintype "input"))
    )
    (net (code "17") (name "Net-(OPTO_EL37_4B-AN)") (class "Default")
      (node (ref "OPTO_EL37_4B") (pin "1") (pinfunction "AN_1") (pintype "unspecified"))
      (node (ref "R7") (pin "2") (pinfunction "2_2") (pintype "input"))
    )
    (net (code "18") (name "Net-(OPTO_EL37_5A-AN)") (class "Default")
      (node (ref "OPTO_EL37_5A") (pin "1") (pinfunction "AN_1") (pintype "unspecified"))
      (node (ref "R17") (pin "2") (pinfunction "2_2") (pintype "input"))
    )
    (net (code "19") (name "Net-(OPTO_EL37_5B-AN)") (class "Default")
      (node (ref "OPTO_EL37_5B") (pin "1") (pinfunction "AN_1") (pintype "unspecified"))
      (node (ref "R16") (pin "2") (pinfunction "2_2") (pintype "input"))
    )
    (net (code "20") (name "Net-(OPTO_EL37_6A-AN)") (class "Default")
      (node (ref "OPTO_EL37_6A") (pin "1") (pinfunction "AN_1") (pintype "unspecified"))
      (node (ref "R8") (pin "2") (pinfunction "2_2") (pintype "input"))
    )
    (net (code "21") (name "Net-(OPTO_EL37_6B-AN)") (class "Default")
      (node (ref "OPTO_EL37_6B") (pin "1") (pinfunction "AN_1") (pintype "unspecified"))
      (node (ref "R9") (pin "2") (pinfunction "2_2") (pintype "input"))
    )
    (net (code "22") (name "Net-(OPTO_EL37_7A-AN)") (class "Default")
      (node (ref "OPTO_EL37_7A") (pin "1") (pinfunction "AN_1") (pintype "unspecified"))
      (node (ref "R10") (pin "2") (pinfunction "2_2") (pintype "input"))
    )
    (net (code "23") (name "Net-(OPTO_EL37_7B-AN)") (class "Default")
      (node (ref "OPTO_EL37_7B") (pin "1") (pinfunction "AN_1") (pintype "unspecified"))
      (node (ref "R11") (pin "2") (pinfunction "2_2") (pintype "input"))
    )
    (net (code "24") (name "Net-(OPTO_EL37_8A-AN)") (class "Default")
      (node (ref "OPTO_EL37_8A") (pin "1") (pinfunction "AN_1") (pintype "unspecified"))
      (node (ref "R12") (pin "2") (pinfunction "2_2") (pintype "input"))
    )
    (net (code "25") (name "Net-(OPTO_EL37_8B-AN)") (class "Default")
      (node (ref "OPTO_EL37_8B") (pin "1") (pinfunction "AN_1") (pintype "unspecified"))
      (node (ref "R13") (pin "2") (pinfunction "2_2") (pintype "input"))
    )
    (net (code "26") (name "Net-(OPTO_EL37_9A-AN)") (class "Default")
      (node (ref "OPTO_EL37_9A") (pin "1") (pinfunction "AN_1") (pintype "unspecified"))
      (node (ref "R14") (pin "2") (pinfunction "2_2") (pintype "input"))
    )
    (net (code "27") (name "Net-(OPTO_EL37_9B-AN)") (class "Default")
      (node (ref "OPTO_EL37_9B") (pin "1") (pinfunction "AN_1") (pintype "unspecified"))
      (node (ref "R15") (pin "2") (pinfunction "2_2") (pintype "input"))
    )
    (net (code "28") (name "Net-(Q1-G)") (class "Default")
      (node (ref "Q1") (pin "4") (pinfunction "G_4") (pintype "unspecified"))
      (node (ref "U26") (pin "5") (pinfunction "G_5") (pintype "unspecified"))
    )
    (net (code "29") (name "Net-(U19-LED0)") (class "Default")
      (node (ref "R55") (pin "2") (pinfunction "2_2") (pintype "input"))
      (node (ref "U19") (pin "6") (pinfunction "LED0_6") (pintype "input"))
    )
    (net (code "30") (name "Net-(U19-LED1)") (class "Default")
      (node (ref "R54") (pin "2") (pinfunction "2_2") (pintype "input"))
      (node (ref "U19") (pin "7") (pinfunction "LED1_7") (pintype "input"))
    )
    (net (code "31") (name "Net-(U19-LED2)") (class "Default")
      (node (ref "R53") (pin "2") (pinfunction "2_2") (pintype "input"))
      (node (ref "U19") (pin "8") (pinfunction "LED2_8") (pintype "input"))
    )
    (net (code "32") (name "Net-(U19-LED3)") (class "Default")
      (node (ref "R52") (pin "2") (pinfunction "2_2") (pintype "input"))
      (node (ref "U19") (pin "9") (pinfunction "LED3_9") (pintype "input"))
    )
    (net (code "33") (name "Net-(U19-LED4)") (class "Default")
      (node (ref "R51") (pin "2") (pinfunction "2_2") (pintype "input"))
      (node (ref "U19") (pin "10") (pinfunction "LED4_10") (pintype "input"))
    )
    (net (code "34") (name "Net-(U19-LED5)") (class "Default")
      (node (ref "R50") (pin "2") (pinfunction "2_2") (pintype "input"))
      (node (ref "U19") (pin "11") (pinfunction "LED5_11") (pintype "input"))
    )
    (net (code "35") (name "Net-(U19-LED6)") (class "Default")
      (node (ref "R65") (pin "1") (pinfunction "1_1") (pintype "input"))
      (node (ref "U19") (pin "12") (pinfunction "LED6_12") (pintype "input"))
    )
    (net (code "36") (name "Net-(U19-LED7)") (class "Default")
      (node (ref "R64") (pin "1") (pinfunction "1_1") (pintype "input"))
      (node (ref "U19") (pin "13") (pinfunction "LED7_13") (pintype "input"))
    )
    (net (code "37") (name "Net-(U19-LED8)") (class "Default")
      (node (ref "R63") (pin "1") (pinfunction "1_1") (pintype "input"))
      (node (ref "U19") (pin "15") (pinfunction "LED8_15") (pintype "input"))
    )
    (net (code "38") (name "Net-(U27-BOOT)") (class "Default")
      (node (ref "C58") (pin "1") (pinfunction "1_1") (pintype "unspecified"))
      (node (ref "U27") (pin "1") (pinfunction "BOOT_1") (pintype "unspecified"))
    )
    (net (code "39") (name "Net-(U27-VSENSE)") (class "Default")
      (node (ref "R27") (pin "1") (pinfunction "1_1") (pintype "input"))
      (node (ref "R28") (pin "2") (pinfunction "2_2") (pintype "input"))
      (node (ref "U27") (pin "4") (pinfunction "VSENSE_4") (pintype "unspecified"))
    )
    (net (code "40") (name "SCL") (class "Default")
      (node (ref "R93") (pin "1") (pinfunction "1_1") (pintype "input"))
      (node (ref "U19") (pin "26") (pinfunction "SCL_26") (pintype "input"))
    )
    (net (code "41") (name "SDA") (class "Default")
      (node (ref "R92") (pin "1") (pinfunction "1_1") (pintype "input"))
      (node (ref "U19") (pin "27") (pinfunction "SDA_27") (pintype "input"))
    )
    (net (code "42") (name "SW1") (class "Default")
      (node (ref "R1") (pin "1") (pinfunction "1_1") (pintype "input"))
      (node (ref "R48") (pin "1") (pinfunction "1_1") (pintype "input"))
      (node (ref "R63") (pin "2") (pinfunction "2_2") (pintype "input"))
    )
    (net (code "43") (name "SW1_A") (class "Default")
      (node (ref "OPTO_EL37_1A") (pin "3") (pinfunction "EM_3") (pintype "unspecified"))
      (node (ref "U1") (pin "4") (pinfunction "4_4") (pintype "unspecified"))
    )
    (net (code "44") (name "SW1_B") (class "Default")
      (node (ref "OPTO_EL37_1B") (pin "3") (pinfunction "EM_3") (pintype "unspecified"))
      (node (ref "U1") (pin "1") (pinfunction "1_1") (pintype "unspecified"))
    )
    (net (code "45") (name "SW2") (class "Default")
      (node (ref "R2") (pin "1") (pinfunction "1_1") (pintype "input"))
      (node (ref "R3") (pin "1") (pinfunction "1_1") (pintype "input"))
      (node (ref "R64") (pin "2") (pinfunction "2_2") (pintype "input"))
    )
    (net (code "46") (name "SW2_A") (class "Default")
      (node (ref "OPTO_EL37_2A") (pin "3") (pinfunction "EM_3") (pintype "unspecified"))
      (node (ref "U2") (pin "4") (pinfunction "4_4") (pintype "unspecified"))
    )
    (net (code "47") (name "SW2_B") (class "Default")
      (node (ref "OPTO_EL37_2B") (pin "3") (pinfunction "EM_3") (pintype "unspecified"))
      (node (ref "U2") (pin "1") (pinfunction "1_1") (pintype "unspecified"))
    )
    (net (code "48") (name "SW3") (class "Default")
      (node (ref "R4") (pin "1") (pinfunction "1_1") (pintype "input"))
      (node (ref "R5") (pin "1") (pinfunction "1_1") (pintype "input"))
      (node (ref "R65") (pin "2") (pinfunction "2_2") (pintype "input"))
    )
    (net (code "49") (name "SW3_A") (class "Default")
      (node (ref "OPTO_EL37_3A") (pin "3") (pinfunction "EM_3") (pintype "unspecified"))
      (node (ref "U3") (pin "4") (pinfunction "4_4") (pintype "unspecified"))
    )
    (net (code "50") (name "SW3_B") (class "Default")
      (node (ref "OPTO_EL37_3B") (pin "3") (pinfunction "EM_3") (pintype "unspecified"))
      (node (ref "U3") (pin "1") (pinfunction "1_1") (pintype "unspecified"))
    )
    (net (code "51") (name "SW4") (class "Default")
      (node (ref "R50") (pin "1") (pinfunction "1_1") (pintype "input"))
      (node (ref "R6") (pin "1") (pinfunction "1_1") (pintype "input"))
      (node (ref "R7") (pin "1") (pinfunction "1_1") (pintype "input"))
    )
    (net (code "52") (name "SW4_A") (class "Default")
      (node (ref "OPTO_EL37_4A") (pin "3") (pinfunction "EM_3") (pintype "unspecified"))
      (node (ref "U4") (pin "4") (pinfunction "4_4") (pintype "unspecified"))
    )
    (net (code "53") (name "SW4_B") (class "Default")
      (node (ref "OPTO_EL37_4B") (pin "3") (pinfunction "EM_3") (pintype "unspecified"))
      (node (ref "U4") (pin "1") (pinfunction "1_1") (pintype "unspecified"))
    )
    (net (code "54") (name "SW5") (class "Default")
      (node (ref "R16") (pin "1") (pinfunction "1_1") (pintype "input"))
      (node (ref "R17") (pin "1") (pinfunction "1_1") (pintype "input"))
      (node (ref "R51") (pin "1") (pinfunction "1_1") (pintype "input"))
    )
    (net (code "55") (name "SW5_A") (class "Default")
      (node (ref "OPTO_EL37_5A") (pin "3") (pinfunction "EM_3") (pintype "unspecified"))
      (node (ref "U9") (pin "4") (pinfunction "4_4") (pintype "unspecified"))
    )
    (net (code "56") (name "SW5_B") (class "Default")
      (node (ref "OPTO_EL37_5B") (pin "3") (pinfunction "EM_3") (pintype "unspecified"))
      (node (ref "U9") (pin "1") (pinfunction "1_1") (pintype "unspecified"))
    )
    (net (code "57") (name "SW6") (class "Default")
      (node (ref "R52") (pin "1") (pinfunction "1_1") (pintype "input"))
      (node (ref "R8") (pin "1") (pinfunction "1_1") (pintype "input"))
      (node (ref "R9") (pin "1") (pinfunction "1_1") (pintype "input"))
    )
    (net (code "58") (name "SW6_A") (class "Default")
      (node (ref "OPTO_EL37_6A") (pin "3") (pinfunction "EM_3") (pintype "unspecified"))
      (node (ref "U5") (pin "4") (pinfunction "4_4") (pintype "unspecified"))
    )
    (net (code "59") (name "SW6_B") (class "Default")
      (node (ref "OPTO_EL37_6B") (pin "3") (pinfunction "EM_3") (pintype "unspecified"))
      (node (ref "U5") (pin "1") (pinfunction "1_1") (pintype "unspecified"))
    )
    (net (code "60") (name "SW7") (class "Default")
      (node (ref "R10") (pin "1") (pinfunction "1_1") (pintype "input"))
      (node (ref "R11") (pin "1") (pinfunction "1_1") (pintype "input"))
      (node (ref "R53") (pin "1") (pinfunction "1_1") (pintype "input"))
    )
    (net (code "61") (name "SW7_A") (class "Default")
      (node (ref "OPTO_EL37_7A") (pin "3") (pinfunction "EM_3") (pintype "unspecified"))
      (node (ref "U6") (pin "4") (pinfunction "4_4") (pintype "unspecified"))
    )
    (net (code "62") (name "SW7_B") (class "Default")
      (node (ref "OPTO_EL37_7B") (pin "3") (pinfunction "EM_3") (pintype "unspecified"))
      (node (ref "U6") (pin "1") (pinfunction "1_1") (pintype "unspecified"))
    )
    (net (code "63") (name "SW8") (class "Default")
      (node (ref "R12") (pin "1") (pinfunction "1_1") (pintype "input"))
      (node (ref "R13") (pin "1") (pinfunction "1_1") (pintype "input"))
      (node (ref "R54") (pin "1") (pinfunction "1_1") (pintype "input"))
    )
    (net (code "64") (name "SW8_A") (class "Default")
      (node (ref "OPTO_EL37_8A") (pin "3") (pinfunction "EM_3") (pintype "unspecified"))
      (node (ref "U7") (pin "4") (pinfunction "4_4") (pintype "unspecified"))
    )
    (net (code "65") (name "SW8_B") (class "Default")
      (node (ref "OPTO_EL37_8B") (pin "3") (pinfunction "EM_3") (pintype "unspecified"))
      (node (ref "U7") (pin "1") (pinfunction "1_1") (pintype "unspecified"))
    )
    (net (code "66") (name "SW9") (class "Default")
      (node (ref "R14") (pin "1") (pinfunction "1_1") (pintype "input"))
      (node (ref "R15") (pin "1") (pinfunction "1_1") (pintype "input"))
      (node (ref "R55") (pin "1") (pinfunction "1_1") (pintype "input"))
    )
    (net (code "67") (name "SW9_A") (class "Default")
      (node (ref "OPTO_EL37_9A") (pin "3") (pinfunction "EM_3") (pintype "unspecified"))
      (node (ref "U8") (pin "4") (pinfunction "4_4") (pintype "unspecified"))
    )
    (net (code "68") (name "SW9_B") (class "Default")
      (node (ref "OPTO_EL37_9B") (pin "3") (pinfunction "EM_3") (pintype "unspecified"))
      (node (ref "U8") (pin "1") (pinfunction "1_1") (pintype "unspecified"))
    )
    (net (code "69") (name "unconnected-(U1-Pad3)") (class "Default")
      (node (ref "U1") (pin "3") (pinfunction "3_3") (pintype "unspecified+no_connect"))
    )
    (net (code "70") (name "unconnected-(U1-Pad6)") (class "Default")
      (node (ref "U1") (pin "6") (pinfunction "6_6") (pintype "unspecified+no_connect"))
    )
    (net (code "71") (name "unconnected-(U2-Pad2)") (class "Default")
      (node (ref "U2") (pin "2") (pinfunction "2_2") (pintype "unspecified+no_connect"))
    )
    (net (code "72") (name "unconnected-(U2-Pad3)") (class "Default")
      (node (ref "U2") (pin "3") (pinfunction "3_3") (pintype "unspecified+no_connect"))
    )
    (net (code "73") (name "unconnected-(U2-Pad5)") (class "Default")
      (node (ref "U2") (pin "5") (pinfunction "5_5") (pintype "unspecified+no_connect"))
    )
    (net (code "74") (name "unconnected-(U2-Pad6)") (class "Default")
      (node (ref "U2") (pin "6") (pinfunction "6_6") (pintype "unspecified+no_connect"))
    )
    (net (code "75") (name "unconnected-(U3-Pad2)") (class "Default")
      (node (ref "U3") (pin "2") (pinfunction "2_2") (pintype "unspecified+no_connect"))
    )
    (net (code "76") (name "unconnected-(U3-Pad3)") (class "Default")
      (node (ref "U3") (pin "3") (pinfunction "3_3") (pintype "unspecified+no_connect"))
    )
    (net (code "77") (name "unconnected-(U3-Pad5)") (class "Default")
      (node (ref "U3") (pin "5") (pinfunction "5_5") (pintype "unspecified+no_connect"))
    )
    (net (code "78") (name "unconnected-(U3-Pad6)") (class "Default")
      (node (ref "U3") (pin "6") (pinfunction "6_6") (pintype "unspecified+no_connect"))
    )
    (net (code "79") (name "unconnected-(U4-Pad2)") (class "Default")
      (node (ref "U4") (pin "2") (pinfunction "2_2") (pintype "unspecified+no_connect"))
    )
    (net (code "80") (name "unconnected-(U4-Pad3)") (class "Default")
      (node (ref "U4") (pin "3") (pinfunction "3_3") (pintype "unspecified+no_connect"))
    )
    (net (code "81") (name "unconnected-(U4-Pad5)") (class "Default")
      (node (ref "U4") (pin "5") (pinfunction "5_5") (pintype "unspecified+no_connect"))
    )
    (net (code "82") (name "unconnected-(U4-Pad6)") (class "Default")
      (node (ref "U4") (pin "6") (pinfunction "6_6") (pintype "unspecified+no_connect"))
    )
    (net (code "83") (name "unconnected-(U5-Pad2)") (class "Default")
      (node (ref "U5") (pin "2") (pinfunction "2_2") (pintype "unspecified+no_connect"))
    )
    (net (code "84") (name "unconnected-(U5-Pad3)") (class "Default")
      (node (ref "U5") (pin "3") (pinfunction "3_3") (pintype "unspecified+no_connect"))
    )
    (net (code "85") (name "unconnected-(U5-Pad5)") (class "Default")
      (node (ref "U5") (pin "5") (pinfunction "5_5") (pintype "unspecified+no_connect"))
    )
    (net (code "86") (name "unconnected-(U5-Pad6)") (class "Default")
      (node (ref "U5") (pin "6") (pinfunction "6_6") (pintype "unspecified+no_connect"))
    )
    (net (code "87") (name "unconnected-(U6-Pad2)") (class "Default")
      (node (ref "U6") (pin "2") (pinfunction "2_2") (pintype "unspecified+no_connect"))
    )
    (net (code "88") (name "unconnected-(U6-Pad3)") (class "Default")
      (node (ref "U6") (pin "3") (pinfunction "3_3") (pintype "unspecified+no_connect"))
    )
    (net (code "89") (name "unconnected-(U6-Pad5)") (class "Default")
      (node (ref "U6") (pin "5") (pinfunction "5_5") (pintype "unspecified+no_connect"))
    )
    (net (code "90") (name "unconnected-(U6-Pad6)") (class "Default")
      (node (ref "U6") (pin "6") (pinfunction "6_6") (pintype "unspecified+no_connect"))
    )
    (net (code "91") (name "unconnected-(U7-Pad2)") (class "Default")
      (node (ref "U7") (pin "2") (pinfunction "2_2") (pintype "unspecified+no_connect"))
    )
    (net (code "92") (name "unconnected-(U7-Pad3)") (class "Default")
      (node (ref "U7") (pin "3") (pinfunction "3_3") (pintype "unspecified+no_connect"))
    )
    (net (code "93") (name "unconnected-(U7-Pad5)") (class "Default")
      (node (ref "U7") (pin "5") (pinfunction "5_5") (pintype "unspecified+no_connect"))
    )
    (net (code "94") (name "unconnected-(U7-Pad6)") (class "Default")
      (node (ref "U7") (pin "6") (pinfunction "6_6") (pintype "unspecified+no_connect"))
    )
    (net (code "95") (name "unconnected-(U8-Pad2)") (class "Default")
      (node (ref "U8") (pin "2") (pinfunction "2_2") (pintype "unspecified+no_connect"))
    )
    (net (code "96") (name "unconnected-(U8-Pad3)") (class "Default")
      (node (ref "U8") (pin "3") (pinfunction "3_3") (pintype "unspecified+no_connect"))
    )
    (net (code "97") (name "unconnected-(U8-Pad5)") (class "Default")
      (node (ref "U8") (pin "5") (pinfunction "5_5") (pintype "unspecified+no_connect"))
    )
    (net (code "98") (name "unconnected-(U8-Pad6)") (class "Default")
      (node (ref "U8") (pin "6") (pinfunction "6_6") (pintype "unspecified+no_connect"))
    )
    (net (code "99") (name "unconnected-(U9-Pad2)") (class "Default")
      (node (ref "U9") (pin "2") (pinfunction "2_2") (pintype "unspecified+no_connect"))
    )
    (net (code "100") (name "unconnected-(U9-Pad3)") (class "Default")
      (node (ref "U9") (pin "3") (pinfunction "3_3") (pintype "unspecified+no_connect"))
    )
    (net (code "101") (name "unconnected-(U9-Pad5)") (class "Default")
      (node (ref "U9") (pin "5") (pinfunction "5_5") (pintype "unspecified+no_connect"))
    )
    (net (code "102") (name "unconnected-(U9-Pad6)") (class "Default")
      (node (ref "U9") (pin "6") (pinfunction "6_6") (pintype "unspecified+no_connect"))
    )
    (net (code "103") (name "unconnected-(U19-A0-Pad1)") (class "Default")
      (node (ref "U19") (pin "1") (pinfunction "A0_1") (pintype "input+no_connect"))
    )
    (net (code "104") (name "unconnected-(U19-A1-Pad2)") (class "Default")
      (node (ref "U19") (pin "2") (pinfunction "A1_2") (pintype "input+no_connect"))
    )
    (net (code "105") (name "unconnected-(U19-A2-Pad3)") (class "Default")
      (node (ref "U19") (pin "3") (pinfunction "A2_3") (pintype "input+no_connect"))
    )
    (net (code "106") (name "unconnected-(U19-A3-Pad4)") (class "Default")
      (node (ref "U19") (pin "4") (pinfunction "A3_4") (pintype "input+no_connect"))
    )
    (net (code "107") (name "unconnected-(U19-A4-Pad5)") (class "Default")
      (node (ref "U19") (pin "5") (pinfunction "A4_5") (pintype "input+no_connect"))
    )
    (net (code "108") (name "unconnected-(U19-A5-Pad24)") (class "Default")
      (node (ref "U19") (pin "24") (pinfunction "A5_24") (pintype "input+no_connect"))
    )
    (net (code "109") (name "unconnected-(U19-LED9-Pad16)") (class "Default")
      (node (ref "U19") (pin "16") (pinfunction "LED9_16") (pintype "input"))
    )
    (net (code "110") (name "unconnected-(U19-LED10-Pad17)") (class "Default")
      (node (ref "U19") (pin "17") (pinfunction "LED10_17") (pintype "input+no_connect"))
    )
    (net (code "111") (name "unconnected-(U19-LED11-Pad18)") (class "Default")
      (node (ref "U19") (pin "18") (pinfunction "LED11_18") (pintype "input+no_connect"))
    )
    (net (code "112") (name "unconnected-(U19-LED12-Pad19)") (class "Default")
      (node (ref "U19") (pin "19") (pinfunction "LED12_19") (pintype "input+no_connect"))
    )
    (net (code "113") (name "unconnected-(U19-LED13-Pad20)") (class "Default")
      (node (ref "U19") (pin "20") (pinfunction "LED13_20") (pintype "input+no_connect"))
    )
    (net (code "114") (name "unconnected-(U19-LED14-Pad21)") (class "Default")
      (node (ref "U19") (pin "21") (pinfunction "LED14_21") (pintype "input+no_connect"))
    )
    (net (code "115") (name "unconnected-(U19-LED15-Pad22)") (class "Default")
      (node (ref "U19") (pin "22") (pinfunction "LED15_22") (pintype "input+no_connect"))
    )
    (net (code "116") (name "unconnected-(U26-NC-Pad1)") (class "Default")
      (node (ref "U26") (pin "1") (pinfunction "NC_1") (pintype "unspecified+no_connect"))
    )
    (net (code "117") (name "unconnected-(U27-ENA-Pad5)") (class "Default")
      (node (ref "U27") (pin "5") (pinfunction "ENA_5") (pintype "unspecified+no_connect"))
    )
    (net (code "118") (name "unconnected-(U27-NC-Pad2)") (class "Default")
      (node (ref "U27") (pin "2") (pinfunction "NC_2") (pintype "unspecified+no_connect"))
    )
    (net (code "119") (name "unconnected-(U27-NC-Pad3)") (class "Default")
      (node (ref "U27") (pin "3") (pinfunction "NC_3") (pintype "unspecified+no_connect"))
    )
  )
)
